# usb.net
KiCad netlist of a schematic drawn in Altium Designer
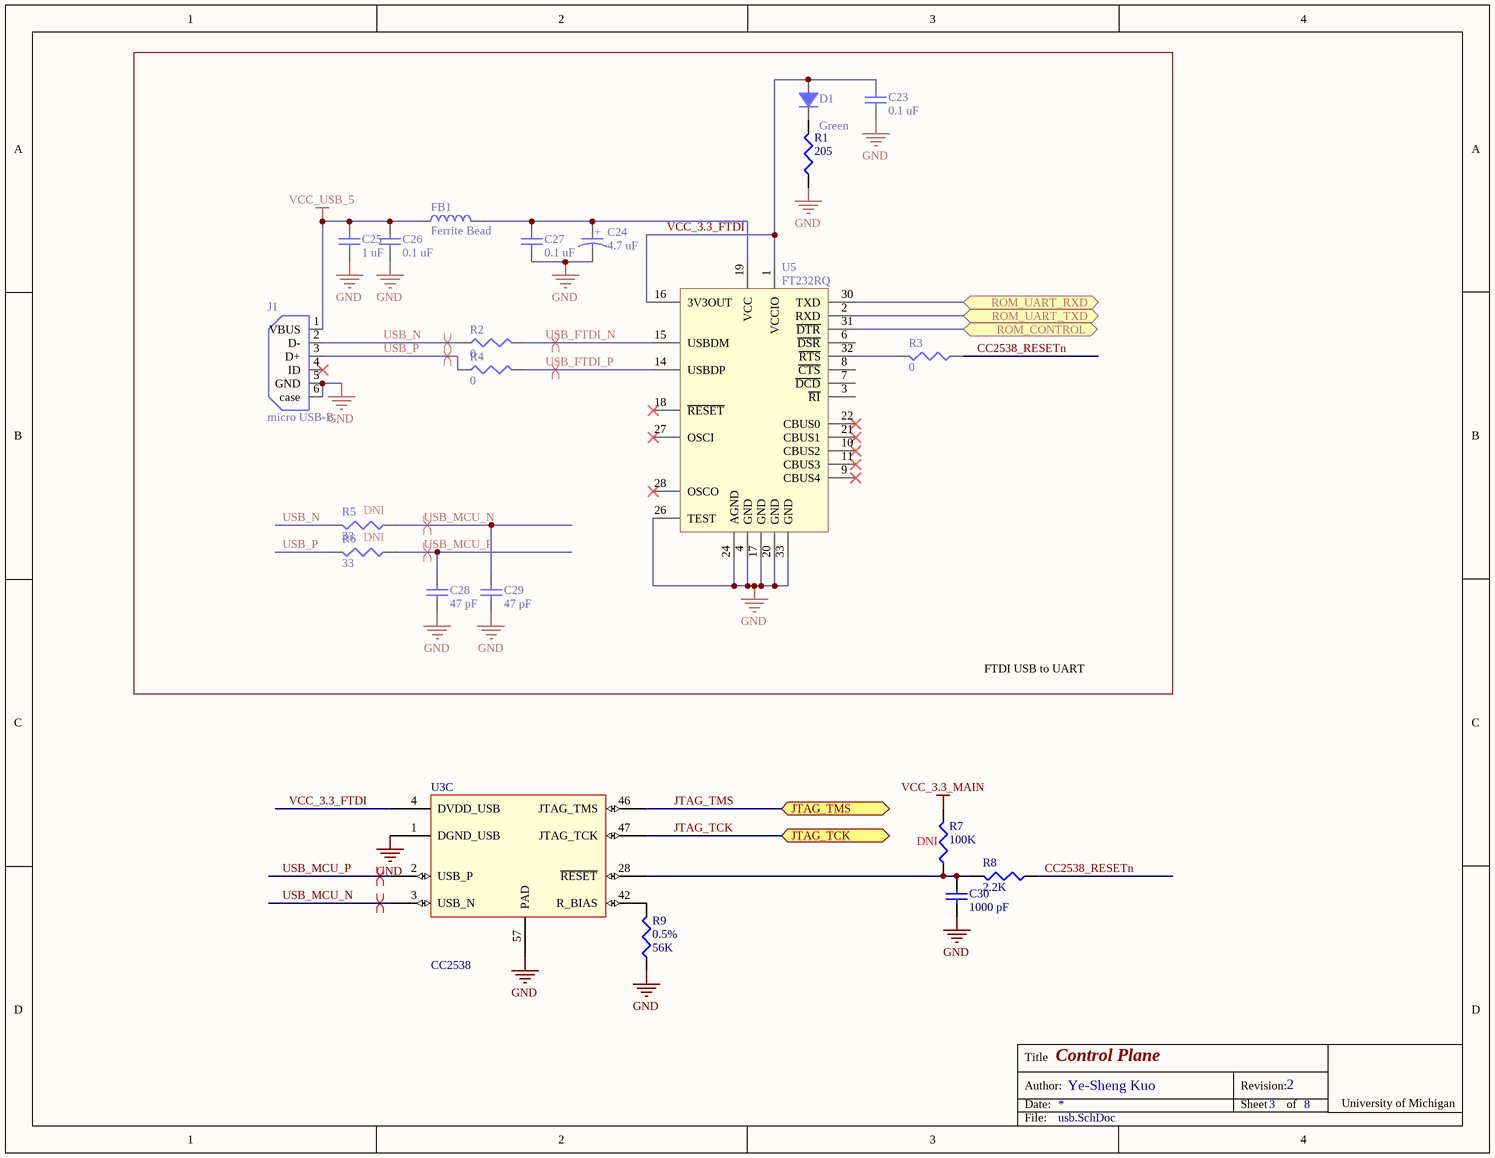
[diagram p0: usb.SchDoc]

(export (version "E")
  (design (tool "Eeschema 10.0.6"))
  (components
    (comp (ref "C23")
      (value "0.1 uF")
      (footprint "0402")
      (description "Ceramic capacitor, 0.1u, 0402 package")
      (fields (field (name "TOLERANCE") "10%") (field (name "Comment") "Ceramic capacitor"))
      (libsource (lib "rlc") (part "C_0.1u_10V_0402_ceramic"))
    )
    (comp (ref "C24")
      (value "4.7 uF")
      (footprint "0603 - Polar Marking")
      (description "Tantalum capacitor, 4.7 uF, 0603 package")
      (fields (field (name "TOLERANCE") "20%") (field (name "Comment") "Tantalum capacitor"))
      (libsource (lib "rlc") (part "C_4.7u_10V_0603_tantalum"))
    )
    (comp (ref "C25")
      (value "1 uF")
      (footprint "0402")
      (description "Ceramic capacitor, 1 uF, 16V, 0402 package")
      (fields (field (name "TOLERANCE") "10%") (field (name "Comment") "Ceramic capacitor"))
      (libsource (lib "rlc") (part "C_1u_16V_0402_ceramic"))
    )
    (comp (ref "C26")
      (value "0.1 uF")
      (footprint "0402")
      (description "Ceramic capacitor, 0.1u, 0402 package")
      (fields (field (name "TOLERANCE") "10%") (field (name "Comment") "Ceramic capacitor"))
      (libsource (lib "rlc") (part "C_0.1u_10V_0402_ceramic"))
    )
    (comp (ref "C27")
      (value "0.1 uF")
      (footprint "0402")
      (description "Ceramic capacitor, 0.1u, 0402 package")
      (fields (field (name "TOLERANCE") "10%") (field (name "Comment") "Ceramic capacitor"))
      (libsource (lib "rlc") (part "C_0.1u_10V_0402_ceramic"))
    )
    (comp (ref "C28")
      (value "47 pF")
      (footprint "0402")
      (description "Ceramic capacitor, 47 pF, 0402 package")
      (fields (field (name "TOLERANCE") "5%") (field (name "Comment") "Ceramic capacitor"))
      (libsource (lib "rlc") (part "C_47p_0402_ceramic"))
    )
    (comp (ref "C29")
      (value "47 pF")
      (footprint "0402")
      (description "Ceramic capacitor, 47 pF, 0402 package")
      (fields (field (name "TOLERANCE") "5%") (field (name "Comment") "Ceramic capacitor"))
      (libsource (lib "rlc") (part "C_47p_0402_ceramic"))
    )
    (comp (ref "C30")
      (value "1000 pF")
      (footprint "0402")
      (description "Ceramic capacitor, 1000 pF, 0402 package")
      (fields (field (name "TOLERANCE") "10%") (field (name "Comment") "Ceramic capacitor"))
      (libsource (lib "rlc") (part "C_1000p_50V_0402_ceramic"))
    )
    (comp (ref "D1")
      (value "LED, Green")
      (footprint "0402 - DIODE")
      (description "LED, Green,  0402")
      (fields (field (name "COLOR") "Green"))
      (libsource (lib "rlc") (part "D_LED_GREEN_0402"))
    )
    (comp (ref "FB1")
      (value "Ferrite Bead")
      (footprint "0402")
      (description "Ferrite Bead, 150 mA, 0402 package")
      (libsource (lib "rlc") (part "FB_150mA_0402"))
    )
    (comp (ref "J1")
      (value "micro USB-B")
      (footprint "Micro USB-B")
      (description "CONN USB MICRO B RECPT SMT R/A")
      (libsource (lib "connectors") (part "Micro USB"))
    )
    (comp (ref "R1")
      (value "205")
      (footprint "0402")
      (description "Chip resistor, 205, 0402 package")
      (fields (field (name "TOLERANCE") "1%") (field (name "POWER") "1/16 W"))
      (libsource (lib "rlc") (part "R_205_0402"))
    )
    (comp (ref "R2")
      (value "0")
      (footprint "0402")
      (description "Chip resistor, 0, 0402 package")
      (fields (field (name "Comment") "Chip resistor"))
      (libsource (lib "rlc") (part "R_0_0402"))
    )
    (comp (ref "R3")
      (value "0")
      (footprint "0402")
      (description "Chip resistor, 0, 0402 package")
      (fields (field (name "Comment") "Chip resistor"))
      (libsource (lib "rlc") (part "R_0_0402"))
    )
    (comp (ref "R4")
      (value "0")
      (footprint "0402")
      (description "Chip resistor, 0, 0402 package")
      (fields (field (name "Comment") "Chip resistor"))
      (libsource (lib "rlc") (part "R_0_0402"))
    )
    (comp (ref "R5")
      (value "33")
      (footprint "0402")
      (description "Chip resistor, 33, 0402 package")
      (fields (field (name "TOLERANCE") "1%") (field (name "POWER") "1/16 W"))
      (libsource (lib "rlc") (part "R_33_0402"))
    )
    (comp (ref "R6")
      (value "33")
      (footprint "0402")
      (description "Chip resistor, 33, 0402 package")
      (fields (field (name "TOLERANCE") "1%") (field (name "POWER") "1/16 W"))
      (libsource (lib "rlc") (part "R_33_0402"))
    )
    (comp (ref "R7")
      (value "100K")
      (footprint "0402")
      (description "Chip resistor, 100K, 0402 package")
      (fields (field (name "TOLERANCE") "1%") (field (name "POWER") "1/16 W"))
      (libsource (lib "rlc") (part "R_100K_0402"))
    )
    (comp (ref "R8")
      (value "2.2K")
      (footprint "0402")
      (description "Chip resistor, 2.2K, 0402 package")
      (fields (field (name "TOLERANCE") "1%") (field (name "POWER") "1/16 W"))
      (libsource (lib "rlc") (part "R_2.2K_0402"))
    )
    (comp (ref "R9")
      (value "56K")
      (footprint "0402")
      (description "Chip resistor, 56K, 0402 package")
      (fields
        (field (name "POWER") "1/16 W")
        (field (name "TOLERANCE") "0.5%")
        (field (name "Comment") "Chip resistor")
      )
      (libsource (lib "rlc") (part "R_56K_0402"))
    )
    (comp (ref "U3")
      (value "CC2538")
      (footprint "QFN56")
      (description "A Powerful System-On-Chip for 2.4-GHz IEEE 802.15.4, 6LoWPAN  and ZigBee Applications")
      (libsource (lib "sdl") (part "CC2538"))
    )
    (comp (ref "U5")
      (value "FT232RQ")
      (footprint "QFN-32")
      (description "FT232R USB UART")
      (libsource (lib "sdl") (part "FT232RQ"))
    )
  )
  (nets
    (net (code "1") (name "/CC2538_RESETn") (class "Default")
      (node (ref "R3") (pin "2") (pintype "passive"))
      (node (ref "R8") (pin "2") (pintype "passive"))
    )
    (net (code "2") (name "/JTAG_TCK") (class "Default")
      (node (ref "U3") (pin "47") (pinfunction "JTAG_TCK_47") (pintype "bidirectional"))
    )
    (net (code "3") (name "/JTAG_TMS") (class "Default")
      (node (ref "U3") (pin "46") (pinfunction "JTAG_TMS_46") (pintype "bidirectional"))
    )
    (net (code "4") (name "/ROM_CONTROL") (class "Default")
      (node (ref "U5") (pin "31") (pinfunction "~{DTR}_31") (pintype "passive"))
    )
    (net (code "5") (name "/ROM_UART_RXD") (class "Default")
      (node (ref "U5") (pin "30") (pinfunction "TXD_30") (pintype "passive"))
    )
    (net (code "6") (name "/ROM_UART_TXD") (class "Default")
      (node (ref "U5") (pin "2") (pinfunction "RXD_2") (pintype "passive"))
    )
    (net (code "7") (name "/USB_FTDI_N") (class "Default")
      (node (ref "R2") (pin "1") (pintype "passive"))
      (node (ref "U5") (pin "15") (pinfunction "USBDM_15") (pintype "passive"))
    )
    (net (code "8") (name "/USB_FTDI_P") (class "Default")
      (node (ref "R4") (pin "1") (pintype "passive"))
      (node (ref "U5") (pin "14") (pinfunction "USBDP_14") (pintype "passive"))
    )
    (net (code "9") (name "/USB_MCU_N") (class "Default")
      (node (ref "C29") (pin "1") (pintype "passive"))
      (node (ref "R5") (pin "2") (pintype "passive"))
      (node (ref "U3") (pin "3") (pinfunction "USB_N_3") (pintype "bidirectional"))
    )
    (net (code "10") (name "/USB_MCU_P") (class "Default")
      (node (ref "C28") (pin "1") (pintype "passive"))
      (node (ref "R6") (pin "2") (pintype "passive"))
      (node (ref "U3") (pin "2") (pinfunction "USB_P_2") (pintype "bidirectional"))
    )
    (net (code "11") (name "/USB_N") (class "Default")
      (node (ref "J1") (pin "2") (pinfunction "D-_2") (pintype "power_in"))
      (node (ref "R2") (pin "2") (pintype "passive"))
      (node (ref "R5") (pin "1") (pintype "passive"))
    )
    (net (code "12") (name "/USB_P") (class "Default")
      (node (ref "J1") (pin "3") (pinfunction "D+_3") (pintype "power_in"))
      (node (ref "R4") (pin "2") (pintype "passive"))
      (node (ref "R6") (pin "1") (pintype "passive"))
    )
    (net (code "13") (name "/VCC_3.3_FTDI") (class "Default")
      (node (ref "C23") (pin "1") (pintype "passive"))
      (node (ref "D1") (pin "1") (pintype "passive"))
      (node (ref "U3") (pin "4") (pinfunction "DVDD_USB_4") (pintype "power_in"))
      (node (ref "U5") (pin "1") (pinfunction "VCCIO_1") (pintype "passive"))
      (node (ref "U5") (pin "16") (pinfunction "3V3OUT_16") (pintype "passive"))
    )
    (net (code "14") (name "GND") (class "Default")
      (node (ref "C23") (pin "2") (pintype "passive"))
      (node (ref "C24") (pin "2") (pintype "passive"))
      (node (ref "C25") (pin "2") (pintype "passive"))
      (node (ref "C26") (pin "2") (pintype "passive"))
      (node (ref "C27") (pin "2") (pintype "passive"))
      (node (ref "C28") (pin "2") (pintype "passive"))
      (node (ref "C29") (pin "2") (pintype "passive"))
      (node (ref "C30") (pin "2") (pintype "passive"))
      (node (ref "J1") (pin "5") (pinfunction "GND_5") (pintype "power_in"))
      (node (ref "J1") (pin "6") (pinfunction "case_6") (pintype "power_in"))
      (node (ref "R1") (pin "2") (pintype "passive"))
      (node (ref "R9") (pin "2") (pintype "passive"))
      (node (ref "U3") (pin "1") (pinfunction "DGND_USB_1") (pintype "power_in"))
      (node (ref "U3") (pin "57") (pinfunction "PAD_57") (pintype "power_in"))
      (node (ref "U5") (pin "17") (pinfunction "GND_17") (pintype "passive"))
      (node (ref "U5") (pin "20") (pinfunction "GND_20") (pintype "passive"))
      (node (ref "U5") (pin "24") (pinfunction "AGND_24") (pintype "passive"))
      (node (ref "U5") (pin "26") (pinfunction "TEST_26") (pintype "passive"))
      (node (ref "U5") (pin "33") (pinfunction "GND_33") (pintype "passive"))
      (node (ref "U5") (pin "4") (pinfunction "GND_4") (pintype "passive"))
    )
    (net (code "15") (name "Net-(D1-Pad2)") (class "Default")
      (node (ref "D1") (pin "2") (pintype "passive"))
      (node (ref "R1") (pin "1") (pintype "passive"))
    )
    (net (code "16") (name "Net-(U3C-R_BIAS)") (class "Default")
      (node (ref "R9") (pin "1") (pintype "passive"))
      (node (ref "U3") (pin "42") (pinfunction "R_BIAS_42") (pintype "bidirectional"))
    )
    (net (code "17") (name "Net-(U3C-~{RESET})") (class "Default")
      (node (ref "C30") (pin "1") (pintype "passive"))
      (node (ref "R7") (pin "2") (pintype "passive"))
      (node (ref "R8") (pin "1") (pintype "passive"))
      (node (ref "U3") (pin "28") (pinfunction "~{RESET}_28") (pintype "bidirectional"))
    )
    (net (code "18") (name "Net-(U5-VCC)") (class "Default")
      (node (ref "C24") (pin "1") (pintype "passive"))
      (node (ref "C27") (pin "1") (pintype "passive"))
      (node (ref "FB1") (pin "1") (pintype "passive"))
      (node (ref "U5") (pin "19") (pinfunction "VCC_19") (pintype "passive"))
    )
    (net (code "19") (name "Net-(U5-~{RTS})") (class "Default")
      (node (ref "R3") (pin "1") (pintype "passive"))
      (node (ref "U5") (pin "32") (pinfunction "~{RTS}_32") (pintype "passive"))
    )
    (net (code "20") (name "VCC_3.3_MAIN") (class "Default") (node (ref "R7") (pin "1") (pintype "passive")))
    (net (code "21") (name "VCC_USB_5") (class "Default")
      (node (ref "C25") (pin "1") (pintype "passive"))
      (node (ref "C26") (pin "1") (pintype "passive"))
      (node (ref "FB1") (pin "2") (pintype "passive"))
      (node (ref "J1") (pin "1") (pinfunction "VBUS_1") (pintype "power_in"))
    )
    (net (code "22") (name "unconnected-(J1-ID-Pad4)") (class "Default")
      (node (ref "J1") (pin "4") (pinfunction "ID_4") (pintype "power_in+no_connect"))
    )
    (net (code "23") (name "unconnected-(U5-CBUS0-Pad22)") (class "Default")
      (node (ref "U5") (pin "22") (pinfunction "CBUS0_22") (pintype "passive+no_connect"))
    )
    (net (code "24") (name "unconnected-(U5-CBUS1-Pad21)") (class "Default")
      (node (ref "U5") (pin "21") (pinfunction "CBUS1_21") (pintype "passive+no_connect"))
    )
    (net (code "25") (name "unconnected-(U5-CBUS2-Pad10)") (class "Default")
      (node (ref "U5") (pin "10") (pinfunction "CBUS2_10") (pintype "passive+no_connect"))
    )
    (net (code "26") (name "unconnected-(U5-CBUS3-Pad11)") (class "Default")
      (node (ref "U5") (pin "11") (pinfunction "CBUS3_11") (pintype "passive+no_connect"))
    )
    (net (code "27") (name "unconnected-(U5-CBUS4-Pad9)") (class "Default")
      (node (ref "U5") (pin "9") (pinfunction "CBUS4_9") (pintype "passive+no_connect"))
    )
    (net (code "28") (name "unconnected-(U5-OSCI-Pad27)") (class "Default")
      (node (ref "U5") (pin "27") (pinfunction "OSCI_27") (pintype "passive+no_connect"))
    )
    (net (code "29") (name "unconnected-(U5-OSCO-Pad28)") (class "Default")
      (node (ref "U5") (pin "28") (pinfunction "OSCO_28") (pintype "passive+no_connect"))
    )
    (net (code "30") (name "unconnected-(U5-~{CTS}-Pad8)") (class "Default")
      (node (ref "U5") (pin "8") (pinfunction "~{CTS}_8") (pintype "passive"))
    )
    (net (code "31") (name "unconnected-(U5-~{DCD}-Pad7)") (class "Default")
      (node (ref "U5") (pin "7") (pinfunction "~{DCD}_7") (pintype "passive"))
    )
    (net (code "32") (name "unconnected-(U5-~{DSR}-Pad6)") (class "Default")
      (node (ref "U5") (pin "6") (pinfunction "~{DSR}_6") (pintype "passive"))
    )
    (net (code "33") (name "unconnected-(U5-~{RESET}-Pad18)") (class "Default")
      (node (ref "U5") (pin "18") (pinfunction "~{RESET}_18") (pintype "passive+no_connect"))
    )
    (net (code "34") (name "unconnected-(U5-~{RI}-Pad3)") (class "Default")
      (node (ref "U5") (pin "3") (pinfunction "~{RI}_3") (pintype "passive"))
    )
  )
)
